# Peak.net
KiCad netlist of a schematic drawn in Altium Designer
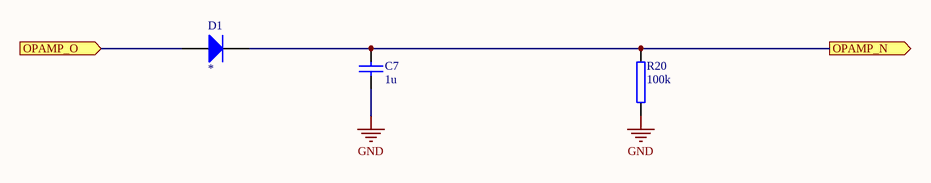
[diagram p0: Peak.SchDoc]

(export (version "E")
  (design (tool "Eeschema 10.0.6"))
  (components
    (comp (ref "C7") (value "1u") (description "Capacitor") (libsource (lib "EceParts") (part "Cap")))
    (comp (ref "D1") (value "*") (description "Diode") (libsource (lib "EceParts") (part "Diode")))
    (comp (ref "R20") (value "100k") (footprint "AXIAL0.4") (libsource (lib "COMSYS301") (part "RES2")))
  )
  (nets
    (net (code "1") (name "/OPAMP_N") (class "Default")
      (node (ref "C7") (pin "1") (pinfunction "1_1") (pintype "passive"))
      (node (ref "D1") (pin "2") (pinfunction "K_2") (pintype "passive"))
      (node (ref "R20") (pin "2") (pinfunction "2_2") (pintype "passive"))
    )
    (net (code "2") (name "/OPAMP_O") (class "Default")
      (node (ref "D1") (pin "1") (pinfunction "A_1") (pintype "passive"))
    )
    (net (code "3") (name "GND") (class "Default")
      (node (ref "C7") (pin "2") (pinfunction "2_2") (pintype "passive"))
      (node (ref "R20") (pin "1") (pinfunction "1_1") (pintype "passive"))
    )
  )
)
